# 03-KSZ9567.net
KiCad netlist of a schematic drawn in Altium Designer
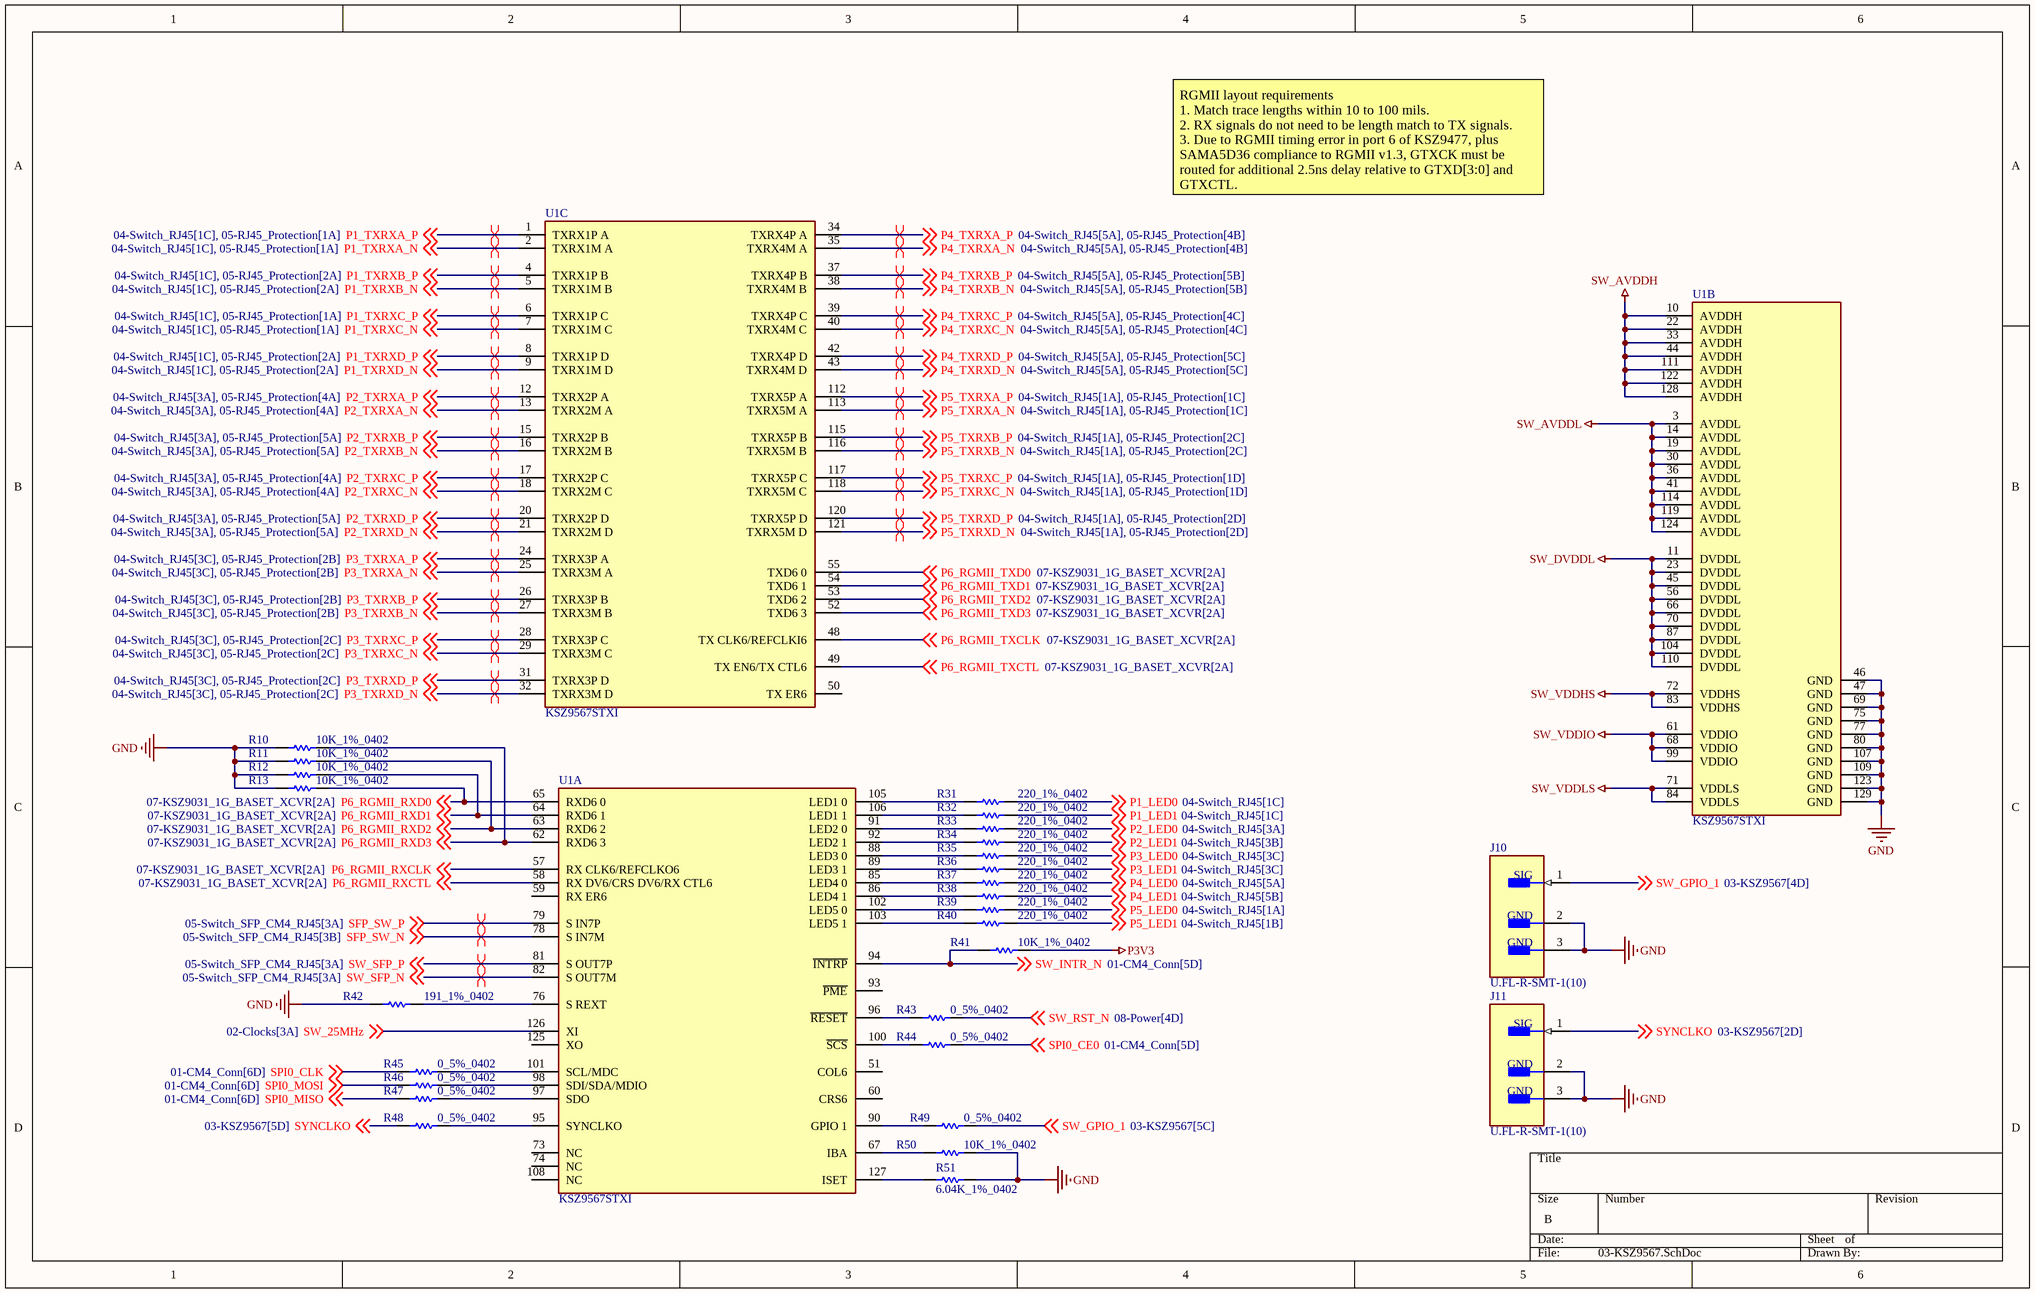
[diagram p0: 03-KSZ9567.SchDoc]

(export (version "E")
  (design (tool "Eeschema 10.0.6"))
  (components
    (comp (ref "J10")
      (value "U.FL-R-SMT-1(10)")
      (footprint "FP-U_FL-R-SMT-1_10-MFG")
      (description "CONN U.FL RCPT STR 50 OHM SMD")
      (libsource (lib "Altium Content Vault") (part "7158abf7d987fa84906f6fb0d115710"))
    )
    (comp (ref "J11")
      (value "U.FL-R-SMT-1(10)")
      (footprint "FP-U_FL-R-SMT-1_10-MFG")
      (description "CONN U.FL RCPT STR 50 OHM SMD")
      (libsource (lib "Altium Content Vault") (part "7158abf7d987fa84906f6fb0d115710"))
    )
    (comp (ref "R10")
      (value "10K_1%_0402")
      (footprint "RESC1005X40X25NL10T10")
      (fields (field (name "MANUFACTURER") "Bourns") (field (name "PART NUMBER") "CR0402-FX-1002GLF"))
      (libsource (lib "Altium Content Vault") (part "RES"))
    )
    (comp (ref "R11")
      (value "10K_1%_0402")
      (footprint "RESC1005X40X25NL10T10")
      (fields (field (name "MANUFACTURER") "Bourns") (field (name "PART NUMBER") "CR0402-FX-1002GLF"))
      (libsource (lib "Altium Content Vault") (part "RES"))
    )
    (comp (ref "R12")
      (value "10K_1%_0402")
      (footprint "RESC1005X40X25NL10T10")
      (fields (field (name "MANUFACTURER") "Bourns") (field (name "PART NUMBER") "CR0402-FX-1002GLF"))
      (libsource (lib "Altium Content Vault") (part "RES"))
    )
    (comp (ref "R13")
      (value "10K_1%_0402")
      (footprint "RESC1005X40X25NL10T10")
      (fields (field (name "MANUFACTURER") "Bourns") (field (name "PART NUMBER") "CR0402-FX-1002GLF"))
      (libsource (lib "Altium Content Vault") (part "RES"))
    )
    (comp (ref "R31")
      (value "220_1%_0402")
      (footprint "RESC1005X40X25NL05T10")
      (fields (field (name "MANUFACTURER") "Yageo / Phycomp") (field (name "PART NUMBER") "RC0402JR-07220RL"))
      (libsource (lib "Altium Content Vault") (part "RES"))
    )
    (comp (ref "R32")
      (value "220_1%_0402")
      (footprint "RESC1005X40X25NL05T10")
      (fields (field (name "MANUFACTURER") "Yageo / Phycomp") (field (name "PART NUMBER") "RC0402JR-07220RL"))
      (libsource (lib "Altium Content Vault") (part "RES"))
    )
    (comp (ref "R33")
      (value "220_1%_0402")
      (footprint "RESC1005X40X25NL05T10")
      (fields (field (name "MANUFACTURER") "Yageo / Phycomp") (field (name "PART NUMBER") "RC0402JR-07220RL"))
      (libsource (lib "Altium Content Vault") (part "RES"))
    )
    (comp (ref "R34")
      (value "220_1%_0402")
      (footprint "RESC1005X40X25NL05T10")
      (fields (field (name "MANUFACTURER") "Yageo / Phycomp") (field (name "PART NUMBER") "RC0402JR-07220RL"))
      (libsource (lib "Altium Content Vault") (part "RES"))
    )
    (comp (ref "R35")
      (value "220_1%_0402")
      (footprint "RESC1005X40X25NL05T10")
      (fields (field (name "MANUFACTURER") "Yageo / Phycomp") (field (name "PART NUMBER") "RC0402JR-07220RL"))
      (libsource (lib "Altium Content Vault") (part "RES"))
    )
    (comp (ref "R36")
      (value "220_1%_0402")
      (footprint "RESC1005X40X25NL05T10")
      (fields (field (name "MANUFACTURER") "Yageo / Phycomp") (field (name "PART NUMBER") "RC0402JR-07220RL"))
      (libsource (lib "Altium Content Vault") (part "RES"))
    )
    (comp (ref "R37")
      (value "220_1%_0402")
      (footprint "RESC1005X40X25NL05T10")
      (fields (field (name "MANUFACTURER") "Yageo / Phycomp") (field (name "PART NUMBER") "RC0402JR-07220RL"))
      (libsource (lib "Altium Content Vault") (part "RES"))
    )
    (comp (ref "R38")
      (value "220_1%_0402")
      (footprint "RESC1005X40X25NL05T10")
      (fields (field (name "MANUFACTURER") "Yageo / Phycomp") (field (name "PART NUMBER") "RC0402JR-07220RL"))
      (libsource (lib "Altium Content Vault") (part "RES"))
    )
    (comp (ref "R39")
      (value "220_1%_0402")
      (footprint "RESC1005X40X25NL05T10")
      (fields (field (name "MANUFACTURER") "Yageo / Phycomp") (field (name "PART NUMBER") "RC0402JR-07220RL"))
      (libsource (lib "Altium Content Vault") (part "RES"))
    )
    (comp (ref "R40")
      (value "220_1%_0402")
      (footprint "RESC1005X40X25NL05T10")
      (fields (field (name "MANUFACTURER") "Yageo / Phycomp") (field (name "PART NUMBER") "RC0402JR-07220RL"))
      (libsource (lib "Altium Content Vault") (part "RES"))
    )
    (comp (ref "R41")
      (value "10K_1%_0402")
      (footprint "RESC1005X40X25NL10T10")
      (fields (field (name "MANUFACTURER") "Bourns") (field (name "PART NUMBER") "CR0402-FX-1002GLF"))
      (libsource (lib "Altium Content Vault") (part "RES"))
    )
    (comp (ref "R42")
      (value "191_1%_0402")
      (footprint "RESC1005X40X25LL10T10")
      (fields (field (name "MANUFACTURER") "Bourns") (field (name "PART NUMBER") "CR0402-FX-1910GLF"))
      (libsource (lib "Altium Content Vault") (part "RES"))
    )
    (comp (ref "R43")
      (value "0_5%_0402")
      (footprint "RESC1005X40X25NL05T10")
      (fields (field (name "MANUFACTURER") "Panasonic") (field (name "PART NUMBER") "ERJ-U020R00X"))
      (libsource (lib "Altium Content Vault") (part "RES"))
    )
    (comp (ref "R44")
      (value "0_5%_0402")
      (footprint "RESC1005X40X25NL05T10")
      (fields (field (name "MANUFACTURER") "Panasonic") (field (name "PART NUMBER") "ERJ-U020R00X"))
      (libsource (lib "Altium Content Vault") (part "RES"))
    )
    (comp (ref "R45")
      (value "0_5%_0402")
      (footprint "RESC1005X40X25NL05T10")
      (fields (field (name "MANUFACTURER") "Panasonic") (field (name "PART NUMBER") "ERJ-U020R00X"))
      (libsource (lib "Altium Content Vault") (part "RES"))
    )
    (comp (ref "R46")
      (value "0_5%_0402")
      (footprint "RESC1005X40X25NL05T10")
      (fields (field (name "MANUFACTURER") "Panasonic") (field (name "PART NUMBER") "ERJ-U020R00X"))
      (libsource (lib "Altium Content Vault") (part "RES"))
    )
    (comp (ref "R47")
      (value "0_5%_0402")
      (footprint "RESC1005X40X25NL05T10")
      (fields (field (name "MANUFACTURER") "Panasonic") (field (name "PART NUMBER") "ERJ-U020R00X"))
      (libsource (lib "Altium Content Vault") (part "RES"))
    )
    (comp (ref "R48")
      (value "0_5%_0402")
      (footprint "RESC1005X40X25NL05T10")
      (fields (field (name "MANUFACTURER") "Panasonic") (field (name "PART NUMBER") "ERJ-U020R00X"))
      (libsource (lib "Altium Content Vault") (part "RES"))
    )
    (comp (ref "R49")
      (value "0_5%_0402")
      (footprint "RESC1005X40X25NL05T10")
      (fields (field (name "MANUFACTURER") "Panasonic") (field (name "PART NUMBER") "ERJ-U020R00X"))
      (libsource (lib "Altium Content Vault") (part "RES"))
    )
    (comp (ref "R50")
      (value "10K_1%_0402")
      (footprint "RESC1005X40X25NL10T10")
      (fields (field (name "MANUFACTURER") "Bourns") (field (name "PART NUMBER") "CR0402-FX-1002GLF"))
      (libsource (lib "Altium Content Vault") (part "RES"))
    )
    (comp (ref "R51")
      (value "6.04K_1%_0402")
      (footprint "RESC1005X40X25NL10T10")
      (fields (field (name "MANUFACTURER") "Multicomp") (field (name "PART NUMBER") "MC00625W040216K04"))
      (libsource (lib "Altium Content Vault") (part "RES"))
    )
    (comp (ref "U1")
      (value "KSZ9567STXI")
      (footprint "FP-C04-418-IPC_A")
      (description "IC ETHERNET SWITCH 7PORT 128TQFP")
      (libsource (lib "Altium Content Vault") (part "0f2b5b9c03f7338342100d589f62d8b"))
    )
  )
  (nets
    (net (code "1") (name "GND") (class "Default")
      (node (ref "J10") (pin "2") (pinfunction "GND_2") (pintype "power_in"))
      (node (ref "J10") (pin "3") (pinfunction "GND_3") (pintype "power_in"))
      (node (ref "J11") (pin "2") (pinfunction "GND_2") (pintype "power_in"))
      (node (ref "J11") (pin "3") (pinfunction "GND_3") (pintype "power_in"))
      (node (ref "R10") (pin "1") (pinfunction "1_1") (pintype "passive"))
      (node (ref "R11") (pin "1") (pinfunction "1_1") (pintype "passive"))
      (node (ref "R12") (pin "1") (pinfunction "1_1") (pintype "passive"))
      (node (ref "R13") (pin "1") (pinfunction "1_1") (pintype "passive"))
      (node (ref "R42") (pin "1") (pinfunction "1_1") (pintype "passive"))
      (node (ref "R50") (pin "2") (pinfunction "2_2") (pintype "passive"))
      (node (ref "R51") (pin "2") (pinfunction "2_2") (pintype "passive"))
      (node (ref "U1") (pin "107") (pinfunction "GND_107") (pintype "passive"))
      (node (ref "U1") (pin "109") (pinfunction "GND_109") (pintype "passive"))
      (node (ref "U1") (pin "123") (pinfunction "GND_123") (pintype "passive"))
      (node (ref "U1") (pin "129") (pinfunction "GND_129") (pintype "passive"))
      (node (ref "U1") (pin "46") (pinfunction "GND_46") (pintype "passive"))
      (node (ref "U1") (pin "47") (pinfunction "GND_47") (pintype "passive"))
      (node (ref "U1") (pin "69") (pinfunction "GND_69") (pintype "passive"))
      (node (ref "U1") (pin "75") (pinfunction "GND_75") (pintype "passive"))
      (node (ref "U1") (pin "77") (pinfunction "GND_77") (pintype "passive"))
      (node (ref "U1") (pin "80") (pinfunction "GND_80") (pintype "passive"))
    )
    (net (code "2") (name "Net-(U1A-GPIO_1)") (class "Default")
      (node (ref "R49") (pin "1") (pinfunction "1_1") (pintype "passive"))
      (node (ref "U1") (pin "90") (pinfunction "GPIO_1_90") (pintype "passive"))
    )
    (net (code "3") (name "Net-(U1A-IBA)") (class "Default")
      (node (ref "R50") (pin "1") (pinfunction "1_1") (pintype "passive"))
      (node (ref "U1") (pin "67") (pinfunction "IBA_67") (pintype "passive"))
    )
    (net (code "4") (name "Net-(U1A-ISET)") (class "Default")
      (node (ref "R51") (pin "1") (pinfunction "1_1") (pintype "passive"))
      (node (ref "U1") (pin "127") (pinfunction "ISET_127") (pintype "passive"))
    )
    (net (code "5") (name "Net-(U1A-LED1_0)") (class "Default")
      (node (ref "R31") (pin "1") (pinfunction "1_1") (pintype "passive"))
      (node (ref "U1") (pin "105") (pinfunction "LED1_0_105") (pintype "passive"))
    )
    (net (code "6") (name "Net-(U1A-LED1_1)") (class "Default")
      (node (ref "R32") (pin "1") (pinfunction "1_1") (pintype "passive"))
      (node (ref "U1") (pin "106") (pinfunction "LED1_1_106") (pintype "passive"))
    )
    (net (code "7") (name "Net-(U1A-LED2_0)") (class "Default")
      (node (ref "R33") (pin "1") (pinfunction "1_1") (pintype "passive"))
      (node (ref "U1") (pin "91") (pinfunction "LED2_0_91") (pintype "passive"))
    )
    (net (code "8") (name "Net-(U1A-LED2_1)") (class "Default")
      (node (ref "R34") (pin "1") (pinfunction "1_1") (pintype "passive"))
      (node (ref "U1") (pin "92") (pinfunction "LED2_1_92") (pintype "passive"))
    )
    (net (code "9") (name "Net-(U1A-LED3_0)") (class "Default")
      (node (ref "R35") (pin "1") (pinfunction "1_1") (pintype "passive"))
      (node (ref "U1") (pin "88") (pinfunction "LED3_0_88") (pintype "passive"))
    )
    (net (code "10") (name "Net-(U1A-LED3_1)") (class "Default")
      (node (ref "R36") (pin "1") (pinfunction "1_1") (pintype "passive"))
      (node (ref "U1") (pin "89") (pinfunction "LED3_1_89") (pintype "passive"))
    )
    (net (code "11") (name "Net-(U1A-LED4_0)") (class "Default")
      (node (ref "R37") (pin "1") (pinfunction "1_1") (pintype "passive"))
      (node (ref "U1") (pin "85") (pinfunction "LED4_0_85") (pintype "passive"))
    )
    (net (code "12") (name "Net-(U1A-LED4_1)") (class "Default")
      (node (ref "R38") (pin "1") (pinfunction "1_1") (pintype "passive"))
      (node (ref "U1") (pin "86") (pinfunction "LED4_1_86") (pintype "passive"))
    )
    (net (code "13") (name "Net-(U1A-LED5_0)") (class "Default")
      (node (ref "R39") (pin "1") (pinfunction "1_1") (pintype "passive"))
      (node (ref "U1") (pin "102") (pinfunction "LED5_0_102") (pintype "passive"))
    )
    (net (code "14") (name "Net-(U1A-LED5_1)") (class "Default")
      (node (ref "R40") (pin "1") (pinfunction "1_1") (pintype "passive"))
      (node (ref "U1") (pin "103") (pinfunction "LED5_1_103") (pintype "passive"))
    )
    (net (code "15") (name "Net-(U1A-SCL{slash}MDC)") (class "Default")
      (node (ref "R45") (pin "2") (pinfunction "2_2") (pintype "passive"))
      (node (ref "U1") (pin "101") (pinfunction "SCL/MDC_101") (pintype "passive"))
    )
    (net (code "16") (name "Net-(U1A-SDI{slash}SDA{slash}MDIO)") (class "Default")
      (node (ref "R46") (pin "2") (pinfunction "2_2") (pintype "passive"))
      (node (ref "U1") (pin "98") (pinfunction "SDI/SDA/MDIO_98") (pintype "passive"))
    )
    (net (code "17") (name "Net-(U1A-SDO)") (class "Default")
      (node (ref "R47") (pin "2") (pinfunction "2_2") (pintype "passive"))
      (node (ref "U1") (pin "97") (pinfunction "SDO_97") (pintype "passive"))
    )
    (net (code "18") (name "Net-(U1A-SYNCLKO)") (class "Default")
      (node (ref "R48") (pin "2") (pinfunction "2_2") (pintype "passive"))
      (node (ref "U1") (pin "95") (pinfunction "SYNCLKO_95") (pintype "passive"))
    )
    (net (code "19") (name "Net-(U1A-S_REXT)") (class "Default")
      (node (ref "R42") (pin "2") (pinfunction "2_2") (pintype "passive"))
      (node (ref "U1") (pin "76") (pinfunction "S_REXT_76") (pintype "passive"))
    )
    (net (code "20") (name "Net-(U1A-~{RESET})") (class "Default")
      (node (ref "R43") (pin "1") (pinfunction "1_1") (pintype "passive"))
      (node (ref "U1") (pin "96") (pinfunction "~{RESET}_96") (pintype "passive"))
    )
    (net (code "21") (name "Net-(U1A-~{SCS})") (class "Default")
      (node (ref "R44") (pin "1") (pinfunction "1_1") (pintype "passive"))
      (node (ref "U1") (pin "100") (pinfunction "~{SCS}_100") (pintype "passive"))
    )
    (net (code "22") (name "P1_LED0") (class "Default")
      (node (ref "R31") (pin "2") (pinfunction "2_2") (pintype "passive"))
    )
    (net (code "23") (name "P1_LED1") (class "Default")
      (node (ref "R32") (pin "2") (pinfunction "2_2") (pintype "passive"))
    )
    (net (code "24") (name "P1_TXRXA_N") (class "Default")
      (node (ref "U1") (pin "2") (pinfunction "TXRX1M_A_2") (pintype "passive"))
    )
    (net (code "25") (name "P1_TXRXA_P") (class "Default")
      (node (ref "U1") (pin "1") (pinfunction "TXRX1P_A_1") (pintype "passive"))
    )
    (net (code "26") (name "P1_TXRXB_N") (class "Default")
      (node (ref "U1") (pin "5") (pinfunction "TXRX1M_B_5") (pintype "passive"))
    )
    (net (code "27") (name "P1_TXRXB_P") (class "Default")
      (node (ref "U1") (pin "4") (pinfunction "TXRX1P_B_4") (pintype "passive"))
    )
    (net (code "28") (name "P1_TXRXC_N") (class "Default")
      (node (ref "U1") (pin "7") (pinfunction "TXRX1M_C_7") (pintype "passive"))
    )
    (net (code "29") (name "P1_TXRXC_P") (class "Default")
      (node (ref "U1") (pin "6") (pinfunction "TXRX1P_C_6") (pintype "passive"))
    )
    (net (code "30") (name "P1_TXRXD_N") (class "Default")
      (node (ref "U1") (pin "9") (pinfunction "TXRX1M_D_9") (pintype "passive"))
    )
    (net (code "31") (name "P1_TXRXD_P") (class "Default")
      (node (ref "U1") (pin "8") (pinfunction "TXRX1P_D_8") (pintype "passive"))
    )
    (net (code "32") (name "P2_LED0") (class "Default")
      (node (ref "R33") (pin "2") (pinfunction "2_2") (pintype "passive"))
    )
    (net (code "33") (name "P2_LED1") (class "Default")
      (node (ref "R34") (pin "2") (pinfunction "2_2") (pintype "passive"))
    )
    (net (code "34") (name "P2_TXRXA_N") (class "Default")
      (node (ref "U1") (pin "13") (pinfunction "TXRX2M_A_13") (pintype "passive"))
    )
    (net (code "35") (name "P2_TXRXA_P") (class "Default")
      (node (ref "U1") (pin "12") (pinfunction "TXRX2P_A_12") (pintype "passive"))
    )
    (net (code "36") (name "P2_TXRXB_N") (class "Default")
      (node (ref "U1") (pin "16") (pinfunction "TXRX2M_B_16") (pintype "passive"))
    )
    (net (code "37") (name "P2_TXRXB_P") (class "Default")
      (node (ref "U1") (pin "15") (pinfunction "TXRX2P_B_15") (pintype "passive"))
    )
    (net (code "38") (name "P2_TXRXC_N") (class "Default")
      (node (ref "U1") (pin "18") (pinfunction "TXRX2M_C_18") (pintype "passive"))
    )
    (net (code "39") (name "P2_TXRXC_P") (class "Default")
      (node (ref "U1") (pin "17") (pinfunction "TXRX2P_C_17") (pintype "passive"))
    )
    (net (code "40") (name "P2_TXRXD_N") (class "Default")
      (node (ref "U1") (pin "21") (pinfunction "TXRX2M_D_21") (pintype "passive"))
    )
    (net (code "41") (name "P2_TXRXD_P") (class "Default")
      (node (ref "U1") (pin "20") (pinfunction "TXRX2P_D_20") (pintype "passive"))
    )
    (net (code "42") (name "P3V3") (class "Default")
      (node (ref "R41") (pin "2") (pinfunction "2_2") (pintype "passive"))
    )
    (net (code "43") (name "P3_LED0") (class "Default")
      (node (ref "R35") (pin "2") (pinfunction "2_2") (pintype "passive"))
    )
    (net (code "44") (name "P3_LED1") (class "Default")
      (node (ref "R36") (pin "2") (pinfunction "2_2") (pintype "passive"))
    )
    (net (code "45") (name "P3_TXRXA_N") (class "Default")
      (node (ref "U1") (pin "25") (pinfunction "TXRX3M_A_25") (pintype "passive"))
    )
    (net (code "46") (name "P3_TXRXA_P") (class "Default")
      (node (ref "U1") (pin "24") (pinfunction "TXRX3P_A_24") (pintype "passive"))
    )
    (net (code "47") (name "P3_TXRXB_N") (class "Default")
      (node (ref "U1") (pin "27") (pinfunction "TXRX3M_B_27") (pintype "passive"))
    )
    (net (code "48") (name "P3_TXRXB_P") (class "Default")
      (node (ref "U1") (pin "26") (pinfunction "TXRX3P_B_26") (pintype "passive"))
    )
    (net (code "49") (name "P3_TXRXC_N") (class "Default")
      (node (ref "U1") (pin "29") (pinfunction "TXRX3M_C_29") (pintype "passive"))
    )
    (net (code "50") (name "P3_TXRXC_P") (class "Default")
      (node (ref "U1") (pin "28") (pinfunction "TXRX3P_C_28") (pintype "passive"))
    )
    (net (code "51") (name "P3_TXRXD_N") (class "Default")
      (node (ref "U1") (pin "32") (pinfunction "TXRX3M_D_32") (pintype "passive"))
    )
    (net (code "52") (name "P3_TXRXD_P") (class "Default")
      (node (ref "U1") (pin "31") (pinfunction "TXRX3P_D_31") (pintype "passive"))
    )
    (net (code "53") (name "P4_LED0") (class "Default")
      (node (ref "R37") (pin "2") (pinfunction "2_2") (pintype "passive"))
    )
    (net (code "54") (name "P4_LED1") (class "Default")
      (node (ref "R38") (pin "2") (pinfunction "2_2") (pintype "passive"))
    )
    (net (code "55") (name "P4_TXRXA_N") (class "Default")
      (node (ref "U1") (pin "35") (pinfunction "TXRX4M_A_35") (pintype "passive"))
    )
    (net (code "56") (name "P4_TXRXA_P") (class "Default")
      (node (ref "U1") (pin "34") (pinfunction "TXRX4P_A_34") (pintype "passive"))
    )
    (net (code "57") (name "P4_TXRXB_N") (class "Default")
      (node (ref "U1") (pin "38") (pinfunction "TXRX4M_B_38") (pintype "passive"))
    )
    (net (code "58") (name "P4_TXRXB_P") (class "Default")
      (node (ref "U1") (pin "37") (pinfunction "TXRX4P_B_37") (pintype "passive"))
    )
    (net (code "59") (name "P4_TXRXC_N") (class "Default")
      (node (ref "U1") (pin "40") (pinfunction "TXRX4M_C_40") (pintype "passive"))
    )
    (net (code "60") (name "P4_TXRXC_P") (class "Default")
      (node (ref "U1") (pin "39") (pinfunction "TXRX4P_C_39") (pintype "passive"))
    )
    (net (code "61") (name "P4_TXRXD_N") (class "Default")
      (node (ref "U1") (pin "43") (pinfunction "TXRX4M_D_43") (pintype "passive"))
    )
    (net (code "62") (name "P4_TXRXD_P") (class "Default")
      (node (ref "U1") (pin "42") (pinfunction "TXRX4P_D_42") (pintype "passive"))
    )
    (net (code "63") (name "P5_LED0") (class "Default")
      (node (ref "R39") (pin "2") (pinfunction "2_2") (pintype "passive"))
    )
    (net (code "64") (name "P5_LED1") (class "Default")
      (node (ref "R40") (pin "2") (pinfunction "2_2") (pintype "passive"))
    )
    (net (code "65") (name "P5_TXRXA_N") (class "Default")
      (node (ref "U1") (pin "113") (pinfunction "TXRX5M_A_113") (pintype "passive"))
    )
    (net (code "66") (name "P5_TXRXA_P") (class "Default")
      (node (ref "U1") (pin "112") (pinfunction "TXRX5P_A_112") (pintype "passive"))
    )
    (net (code "67") (name "P5_TXRXB_N") (class "Default")
      (node (ref "U1") (pin "116") (pinfunction "TXRX5M_B_116") (pintype "passive"))
    )
    (net (code "68") (name "P5_TXRXB_P") (class "Default")
      (node (ref "U1") (pin "115") (pinfunction "TXRX5P_B_115") (pintype "passive"))
    )
    (net (code "69") (name "P5_TXRXC_N") (class "Default")
      (node (ref "U1") (pin "118") (pinfunction "TXRX5M_C_118") (pintype "passive"))
    )
    (net (code "70") (name "P5_TXRXC_P") (class "Default")
      (node (ref "U1") (pin "117") (pinfunction "TXRX5P_C_117") (pintype "passive"))
    )
    (net (code "71") (name "P5_TXRXD_N") (class "Default")
      (node (ref "U1") (pin "121") (pinfunction "TXRX5M_D_121") (pintype "passive"))
    )
    (net (code "72") (name "P5_TXRXD_P") (class "Default")
      (node (ref "U1") (pin "120") (pinfunction "TXRX5P_D_120") (pintype "passive"))
    )
    (net (code "73") (name "P6_RGMII_RXCLK") (class "Default")
      (node (ref "U1") (pin "57") (pinfunction "RX_CLK6/REFCLKO6_57") (pintype "passive"))
    )
    (net (code "74") (name "P6_RGMII_RXCTL") (class "Default")
      (node (ref "U1") (pin "58") (pinfunction "RX_DV6/CRS_DV6/RX_CTL6_58") (pintype "passive"))
    )
    (net (code "75") (name "P6_RGMII_RXD0") (class "Default")
      (node (ref "R13") (pin "2") (pinfunction "2_2") (pintype "passive"))
      (node (ref "U1") (pin "65") (pinfunction "RXD6_0_65") (pintype "passive"))
    )
    (net (code "76") (name "P6_RGMII_RXD1") (class "Default")
      (node (ref "R12") (pin "2") (pinfunction "2_2") (pintype "passive"))
      (node (ref "U1") (pin "64") (pinfunction "RXD6_1_64") (pintype "passive"))
    )
    (net (code "77") (name "P6_RGMII_RXD2") (class "Default")
      (node (ref "R11") (pin "2") (pinfunction "2_2") (pintype "passive"))
      (node (ref "U1") (pin "63") (pinfunction "RXD6_2_63") (pintype "passive"))
    )
    (net (code "78") (name "P6_RGMII_RXD3") (class "Default")
      (node (ref "R10") (pin "2") (pinfunction "2_2") (pintype "passive"))
      (node (ref "U1") (pin "62") (pinfunction "RXD6_3_62") (pintype "passive"))
    )
    (net (code "79") (name "P6_RGMII_TXCLK") (class "Default")
      (node (ref "U1") (pin "48") (pinfunction "TX_CLK6/REFCLKI6_48") (pintype "passive"))
    )
    (net (code "80") (name "P6_RGMII_TXCTL") (class "Default")
      (node (ref "U1") (pin "49") (pinfunction "TX_EN6/TX_CTL6_49") (pintype "passive"))
    )
    (net (code "81") (name "P6_RGMII_TXD0") (class "Default")
      (node (ref "U1") (pin "55") (pinfunction "TXD6_0_55") (pintype "passive"))
    )
    (net (code "82") (name "P6_RGMII_TXD1") (class "Default")
      (node (ref "U1") (pin "54") (pinfunction "TXD6_1_54") (pintype "passive"))
    )
    (net (code "83") (name "P6_RGMII_TXD2") (class "Default")
      (node (ref "U1") (pin "53") (pinfunction "TXD6_2_53") (pintype "passive"))
    )
    (net (code "84") (name "P6_RGMII_TXD3") (class "Default")
      (node (ref "U1") (pin "52") (pinfunction "TXD6_3_52") (pintype "passive"))
    )
    (net (code "85") (name "SFP_SW_N") (class "Default")
      (node (ref "U1") (pin "78") (pinfunction "S_IN7M_78") (pintype "passive"))
    )
    (net (code "86") (name "SFP_SW_P") (class "Default")
      (node (ref "U1") (pin "79") (pinfunction "S_IN7P_79") (pintype "passive"))
    )
    (net (code "87") (name "SPI0_CE0") (class "Default")
      (node (ref "R44") (pin "2") (pinfunction "2_2") (pintype "passive"))
    )
    (net (code "88") (name "SPI0_CLK") (class "Default")
      (node (ref "R45") (pin "1") (pinfunction "1_1") (pintype "passive"))
    )
    (net (code "89") (name "SPI0_MISO") (class "Default")
      (node (ref "R47") (pin "1") (pinfunction "1_1") (pintype "passive"))
    )
    (net (code "90") (name "SPI0_MOSI") (class "Default")
      (node (ref "R46") (pin "1") (pinfunction "1_1") (pintype "passive"))
    )
    (net (code "91") (name "SW_25MHz") (class "Default")
      (node (ref "U1") (pin "126") (pinfunction "XI_126") (pintype "passive"))
    )
    (net (code "92") (name "SW_AVDDH") (class "Default")
      (node (ref "U1") (pin "10") (pinfunction "AVDDH_10") (pintype "passive"))
      (node (ref "U1") (pin "111") (pinfunction "AVDDH_111") (pintype "passive"))
      (node (ref "U1") (pin "122") (pinfunction "AVDDH_122") (pintype "passive"))
      (node (ref "U1") (pin "128") (pinfunction "AVDDH_128") (pintype "passive"))
      (node (ref "U1") (pin "22") (pinfunction "AVDDH_22") (pintype "passive"))
      (node (ref "U1") (pin "33") (pinfunction "AVDDH_33") (pintype "passive"))
      (node (ref "U1") (pin "44") (pinfunction "AVDDH_44") (pintype "passive"))
    )
    (net (code "93") (name "SW_AVDDL") (class "Default")
      (node (ref "U1") (pin "114") (pinfunction "AVDDL_114") (pintype "passive"))
      (node (ref "U1") (pin "119") (pinfunction "AVDDL_119") (pintype "passive"))
      (node (ref "U1") (pin "124") (pinfunction "AVDDL_124") (pintype "passive"))
      (node (ref "U1") (pin "14") (pinfunction "AVDDL_14") (pintype "passive"))
      (node (ref "U1") (pin "19") (pinfunction "AVDDL_19") (pintype "passive"))
      (node (ref "U1") (pin "3") (pinfunction "AVDDL_3") (pintype "passive"))
      (node (ref "U1") (pin "30") (pinfunction "AVDDL_30") (pintype "passive"))
      (node (ref "U1") (pin "36") (pinfunction "AVDDL_36") (pintype "passive"))
      (node (ref "U1") (pin "41") (pinfunction "AVDDL_41") (pintype "passive"))
    )
    (net (code "94") (name "SW_DVDDL") (class "Default")
      (node (ref "U1") (pin "104") (pinfunction "DVDDL_104") (pintype "passive"))
      (node (ref "U1") (pin "11") (pinfunction "DVDDL_11") (pintype "passive"))
      (node (ref "U1") (pin "110") (pinfunction "DVDDL_110") (pintype "passive"))
      (node (ref "U1") (pin "23") (pinfunction "DVDDL_23") (pintype "passive"))
      (node (ref "U1") (pin "45") (pinfunction "DVDDL_45") (pintype "passive"))
      (node (ref "U1") (pin "56") (pinfunction "DVDDL_56") (pintype "passive"))
      (node (ref "U1") (pin "66") (pinfunction "DVDDL_66") (pintype "passive"))
      (node (ref "U1") (pin "70") (pinfunction "DVDDL_70") (pintype "passive"))
      (node (ref "U1") (pin "87") (pinfunction "DVDDL_87") (pintype "passive"))
    )
    (net (code "95") (name "SW_GPIO_1") (class "Default")
      (node (ref "J10") (pin "1") (pinfunction "SIG_1") (pintype "input"))
      (node (ref "R49") (pin "2") (pinfunction "2_2") (pintype "passive"))
    )
    (net (code "96") (name "SW_INTR_N") (class "Default")
      (node (ref "R41") (pin "1") (pinfunction "1_1") (pintype "passive"))
      (node (ref "U1") (pin "94") (pinfunction "~{INTRP}_94") (pintype "passive"))
    )
    (net (code "97") (name "SW_RST_N") (class "Default")
      (node (ref "R43") (pin "2") (pinfunction "2_2") (pintype "passive"))
    )
    (net (code "98") (name "SW_SFP_N") (class "Default")
      (node (ref "U1") (pin "82") (pinfunction "S_OUT7M_82") (pintype "passive"))
    )
    (net (code "99") (name "SW_SFP_P") (class "Default")
      (node (ref "U1") (pin "81") (pinfunction "S_OUT7P_81") (pintype "passive"))
    )
    (net (code "100") (name "SW_VDDHS") (class "Default")
      (node (ref "U1") (pin "72") (pinfunction "VDDHS_72") (pintype "passive"))
      (node (ref "U1") (pin "83") (pinfunction "VDDHS_83") (pintype "passive"))
    )
    (net (code "101") (name "SW_VDDIO") (class "Default")
      (node (ref "U1") (pin "61") (pinfunction "VDDIO_61") (pintype "passive"))
      (node (ref "U1") (pin "68") (pinfunction "VDDIO_68") (pintype "passive"))
      (node (ref "U1") (pin "99") (pinfunction "VDDIO_99") (pintype "passive"))
    )
    (net (code "102") (name "SW_VDDLS") (class "Default")
      (node (ref "U1") (pin "71") (pinfunction "VDDLS_71") (pintype "passive"))
      (node (ref "U1") (pin "84") (pinfunction "VDDLS_84") (pintype "passive"))
    )
    (net (code "103") (name "SYNCLKO") (class "Default")
      (node (ref "J11") (pin "1") (pinfunction "SIG_1") (pintype "input"))
      (node (ref "R48") (pin "1") (pinfunction "1_1") (pintype "passive"))
    )
    (net (code "104") (name "unconnected-(U1A-COL6-Pad51)") (class "Default")
      (node (ref "U1") (pin "51") (pinfunction "COL6_51") (pintype "passive"))
    )
    (net (code "105") (name "unconnected-(U1A-CRS6-Pad60)") (class "Default")
      (node (ref "U1") (pin "60") (pinfunction "CRS6_60") (pintype "passive"))
    )
    (net (code "106") (name "unconnected-(U1A-NC-Pad73)") (class "Default")
      (node (ref "U1") (pin "73") (pinfunction "NC_73") (pintype "passive"))
    )
    (net (code "107") (name "unconnected-(U1A-NC-Pad74)") (class "Default")
      (node (ref "U1") (pin "74") (pinfunction "NC_74") (pintype "passive"))
    )
    (net (code "108") (name "unconnected-(U1A-NC-Pad108)") (class "Default")
      (node (ref "U1") (pin "108") (pinfunction "NC_108") (pintype "passive"))
    )
    (net (code "109") (name "unconnected-(U1A-RX_ER6-Pad59)") (class "Default")
      (node (ref "U1") (pin "59") (pinfunction "RX_ER6_59") (pintype "passive"))
    )
    (net (code "110") (name "unconnected-(U1A-XO-Pad125)") (class "Default")
      (node (ref "U1") (pin "125") (pinfunction "XO_125") (pintype "passive"))
    )
    (net (code "111") (name "unconnected-(U1A-~{PME}-Pad93)") (class "Default")
      (node (ref "U1") (pin "93") (pinfunction "~{PME}_93") (pintype "passive"))
    )
    (net (code "112") (name "unconnected-(U1C-TX_ER6-Pad50)") (class "Default")
      (node (ref "U1") (pin "50") (pinfunction "TX_ER6_50") (pintype "passive"))
    )
  )
)
